# CHESSmate_CPU.net
KiCad netlist of a schematic drawn in EAGLE
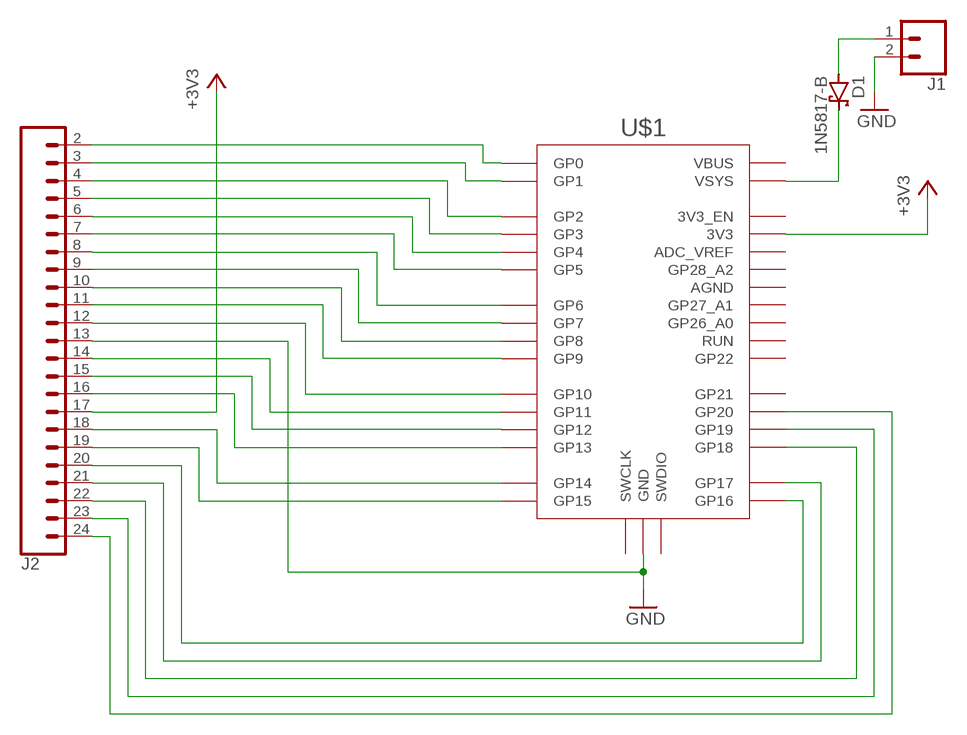
[diagram p0: schematic, sheet 1]

(export (version "E")
  (design (tool "Eeschema 10.0.6"))
  (components
    (comp (ref "D1")
      (value "1N5817-B")
      (footprint "eagle-import:DO41-7.6")
      (libsource (lib "eagle-import") (part "1N5817-B"))
    )
    (comp (ref "J1")
      (value "CONN_02")
      (footprint "eagle-import:1X02")
      (libsource (lib "eagle-import") (part "CONN_02"))
    )
    (comp (ref "J2")
      (value "CONN_23")
      (footprint "eagle-import:1X23")
      (libsource (lib "eagle-import") (part "CONN_23"))
    )
    (comp (ref "U$1")
      (value "RPI_PICO-TH")
      (footprint "eagle-import:RPI_PICO_TH")
      (libsource (lib "eagle-import") (part "RPI_PICO-TH"))
    )
  )
  (nets
    (net (code "1") (name "+3V3") (class "Default")
      (node (ref "J2") (pin "17") (pinfunction "17_17") (pintype "passive"))
      (node (ref "U$1") (pin "3V3") (pinfunction "3V3_3V3") (pintype "bidirectional"))
    )
    (net (code "2") (name "GND") (class "Default")
      (node (ref "J1") (pin "2") (pinfunction "2_2") (pintype "passive"))
      (node (ref "J2") (pin "13") (pinfunction "13_13") (pintype "passive"))
      (node (ref "U$1") (pin "GND@1") (pinfunction "GND_GND@1") (pintype "bidirectional"))
      (node (ref "U$1") (pin "GND@2") (pinfunction "GND_GND@2") (pintype "bidirectional"))
      (node (ref "U$1") (pin "GND@3") (pinfunction "GND_GND@3") (pintype "bidirectional"))
      (node (ref "U$1") (pin "GND@4") (pinfunction "GND_GND@4") (pintype "bidirectional"))
      (node (ref "U$1") (pin "GND@5") (pinfunction "GND_GND@5") (pintype "bidirectional"))
      (node (ref "U$1") (pin "GND@6") (pinfunction "GND_GND@6") (pintype "bidirectional"))
      (node (ref "U$1") (pin "GND@7") (pinfunction "GND_GND@7") (pintype "bidirectional"))
      (node (ref "U$1") (pin "GND@8") (pinfunction "GND_GND@8") (pintype "bidirectional"))
    )
    (net (code "3") (name "Net-(D1-PadA)") (class "Default")
      (node (ref "D1") (pin "A") (pinfunction "A_A") (pintype "passive"))
      (node (ref "J1") (pin "1") (pinfunction "1_1") (pintype "passive"))
    )
    (net (code "4") (name "Net-(D1-PadC)") (class "Default")
      (node (ref "D1") (pin "C") (pinfunction "C_C") (pintype "passive"))
      (node (ref "U$1") (pin "VSYS") (pinfunction "VSYS_VSYS") (pintype "bidirectional"))
    )
    (net (code "5") (name "Net-(J2-Pad2)") (class "Default")
      (node (ref "J2") (pin "2") (pinfunction "2_2") (pintype "passive"))
      (node (ref "U$1") (pin "GP0") (pinfunction "GP0_GP0") (pintype "bidirectional"))
    )
    (net (code "6") (name "Net-(J2-Pad3)") (class "Default")
      (node (ref "J2") (pin "3") (pinfunction "3_3") (pintype "passive"))
      (node (ref "U$1") (pin "GP1") (pinfunction "GP1_GP1") (pintype "bidirectional"))
    )
    (net (code "7") (name "Net-(J2-Pad4)") (class "Default")
      (node (ref "J2") (pin "4") (pinfunction "4_4") (pintype "passive"))
      (node (ref "U$1") (pin "GP2") (pinfunction "GP2_GP2") (pintype "bidirectional"))
    )
    (net (code "8") (name "Net-(J2-Pad5)") (class "Default")
      (node (ref "J2") (pin "5") (pinfunction "5_5") (pintype "passive"))
      (node (ref "U$1") (pin "GP3") (pinfunction "GP3_GP3") (pintype "bidirectional"))
    )
    (net (code "9") (name "Net-(J2-Pad6)") (class "Default")
      (node (ref "J2") (pin "6") (pinfunction "6_6") (pintype "passive"))
      (node (ref "U$1") (pin "GP4") (pinfunction "GP4_GP4") (pintype "bidirectional"))
    )
    (net (code "10") (name "Net-(J2-Pad7)") (class "Default")
      (node (ref "J2") (pin "7") (pinfunction "7_7") (pintype "passive"))
      (node (ref "U$1") (pin "GP5") (pinfunction "GP5_GP5") (pintype "bidirectional"))
    )
    (net (code "11") (name "Net-(J2-Pad8)") (class "Default")
      (node (ref "J2") (pin "8") (pinfunction "8_8") (pintype "passive"))
      (node (ref "U$1") (pin "GP6") (pinfunction "GP6_GP6") (pintype "bidirectional"))
    )
    (net (code "12") (name "Net-(J2-Pad9)") (class "Default")
      (node (ref "J2") (pin "9") (pinfunction "9_9") (pintype "passive"))
      (node (ref "U$1") (pin "GP7") (pinfunction "GP7_GP7") (pintype "bidirectional"))
    )
    (net (code "13") (name "Net-(J2-Pad10)") (class "Default")
      (node (ref "J2") (pin "10") (pinfunction "10_10") (pintype "passive"))
      (node (ref "U$1") (pin "GP8") (pinfunction "GP8_GP8") (pintype "bidirectional"))
    )
    (net (code "14") (name "Net-(J2-Pad11)") (class "Default")
      (node (ref "J2") (pin "11") (pinfunction "11_11") (pintype "passive"))
      (node (ref "U$1") (pin "GP9") (pinfunction "GP9_GP9") (pintype "bidirectional"))
    )
    (net (code "15") (name "Net-(J2-Pad12)") (class "Default")
      (node (ref "J2") (pin "12") (pinfunction "12_12") (pintype "passive"))
      (node (ref "U$1") (pin "GP10") (pinfunction "GP10_GP10") (pintype "bidirectional"))
    )
    (net (code "16") (name "Net-(J2-Pad14)") (class "Default")
      (node (ref "J2") (pin "14") (pinfunction "14_14") (pintype "passive"))
      (node (ref "U$1") (pin "GP11") (pinfunction "GP11_GP11") (pintype "bidirectional"))
    )
    (net (code "17") (name "Net-(J2-Pad15)") (class "Default")
      (node (ref "J2") (pin "15") (pinfunction "15_15") (pintype "passive"))
      (node (ref "U$1") (pin "GP12") (pinfunction "GP12_GP12") (pintype "bidirectional"))
    )
    (net (code "18") (name "Net-(J2-Pad16)") (class "Default")
      (node (ref "J2") (pin "16") (pinfunction "16_16") (pintype "passive"))
      (node (ref "U$1") (pin "GP13") (pinfunction "GP13_GP13") (pintype "bidirectional"))
    )
    (net (code "19") (name "Net-(J2-Pad18)") (class "Default")
      (node (ref "J2") (pin "18") (pinfunction "18_18") (pintype "passive"))
      (node (ref "U$1") (pin "GP14") (pinfunction "GP14_GP14") (pintype "bidirectional"))
    )
    (net (code "20") (name "Net-(J2-Pad19)") (class "Default")
      (node (ref "J2") (pin "19") (pinfunction "19_19") (pintype "passive"))
      (node (ref "U$1") (pin "GP15") (pinfunction "GP15_GP15") (pintype "bidirectional"))
    )
    (net (code "21") (name "Net-(J2-Pad20)") (class "Default")
      (node (ref "J2") (pin "20") (pinfunction "20_20") (pintype "passive"))
      (node (ref "U$1") (pin "GP16") (pinfunction "GP16_GP16") (pintype "bidirectional"))
    )
    (net (code "22") (name "Net-(J2-Pad21)") (class "Default")
      (node (ref "J2") (pin "21") (pinfunction "21_21") (pintype "passive"))
      (node (ref "U$1") (pin "GP17") (pinfunction "GP17_GP17") (pintype "bidirectional"))
    )
    (net (code "23") (name "Net-(J2-Pad22)") (class "Default")
      (node (ref "J2") (pin "22") (pinfunction "22_22") (pintype "passive"))
      (node (ref "U$1") (pin "GP18") (pinfunction "GP18_GP18") (pintype "bidirectional"))
    )
    (net (code "24") (name "Net-(J2-Pad23)") (class "Default")
      (node (ref "J2") (pin "23") (pinfunction "23_23") (pintype "passive"))
      (node (ref "U$1") (pin "GP19") (pinfunction "GP19_GP19") (pintype "bidirectional"))
    )
    (net (code "25") (name "Net-(J2-Pad24)") (class "Default")
      (node (ref "J2") (pin "24") (pinfunction "24_24") (pintype "passive"))
      (node (ref "U$1") (pin "GP20") (pinfunction "GP20_GP20") (pintype "bidirectional"))
    )
    (net (code "26") (name "unconnected-(U$1-Pad3V3_EN)") (class "Default")
      (node (ref "U$1") (pin "3V3_EN") (pinfunction "3V3_EN_3V3_EN") (pintype "bidirectional"))
    )
    (net (code "27") (name "unconnected-(U$1-PadADC_VREF)") (class "Default")
      (node (ref "U$1") (pin "ADC_VREF") (pinfunction "ADC_VREF_ADC_VREF") (pintype "bidirectional"))
    )
    (net (code "28") (name "unconnected-(U$1-PadAGND)") (class "Default")
      (node (ref "U$1") (pin "AGND") (pinfunction "AGND_AGND") (pintype "bidirectional"))
    )
    (net (code "29") (name "unconnected-(U$1-PadGP21)") (class "Default")
      (node (ref "U$1") (pin "GP21") (pinfunction "GP21_GP21") (pintype "bidirectional"))
    )
    (net (code "30") (name "unconnected-(U$1-PadGP22)") (class "Default")
      (node (ref "U$1") (pin "GP22") (pinfunction "GP22_GP22") (pintype "bidirectional"))
    )
    (net (code "31") (name "unconnected-(U$1-PadGP26_A0)") (class "Default")
      (node (ref "U$1") (pin "GP26_A0") (pinfunction "GP26_A0_GP26_A0") (pintype "bidirectional"))
    )
    (net (code "32") (name "unconnected-(U$1-PadGP27_A1)") (class "Default")
      (node (ref "U$1") (pin "GP27_A1") (pinfunction "GP27_A1_GP27_A1") (pintype "bidirectional"))
    )
    (net (code "33") (name "unconnected-(U$1-PadGP28_A2)") (class "Default")
      (node (ref "U$1") (pin "GP28_A2") (pinfunction "GP28_A2_GP28_A2") (pintype "bidirectional"))
    )
    (net (code "34") (name "unconnected-(U$1-PadRUN)") (class "Default")
      (node (ref "U$1") (pin "RUN") (pinfunction "RUN_RUN") (pintype "bidirectional"))
    )
    (net (code "35") (name "unconnected-(U$1-PadSWCLK)") (class "Default")
      (node (ref "U$1") (pin "SWCLK") (pinfunction "SWCLK_SWCLK") (pintype "bidirectional"))
    )
    (net (code "36") (name "unconnected-(U$1-PadSWDIO)") (class "Default")
      (node (ref "U$1") (pin "SWDIO") (pinfunction "SWDIO_SWDIO") (pintype "bidirectional"))
    )
    (net (code "37") (name "unconnected-(U$1-PadVBUS)") (class "Default")
      (node (ref "U$1") (pin "VBUS") (pinfunction "VBUS_VBUS") (pintype "bidirectional"))
    )
  )
)
